# debouncersimple.net
KiCad netlist of a schematic drawn in EAGLE
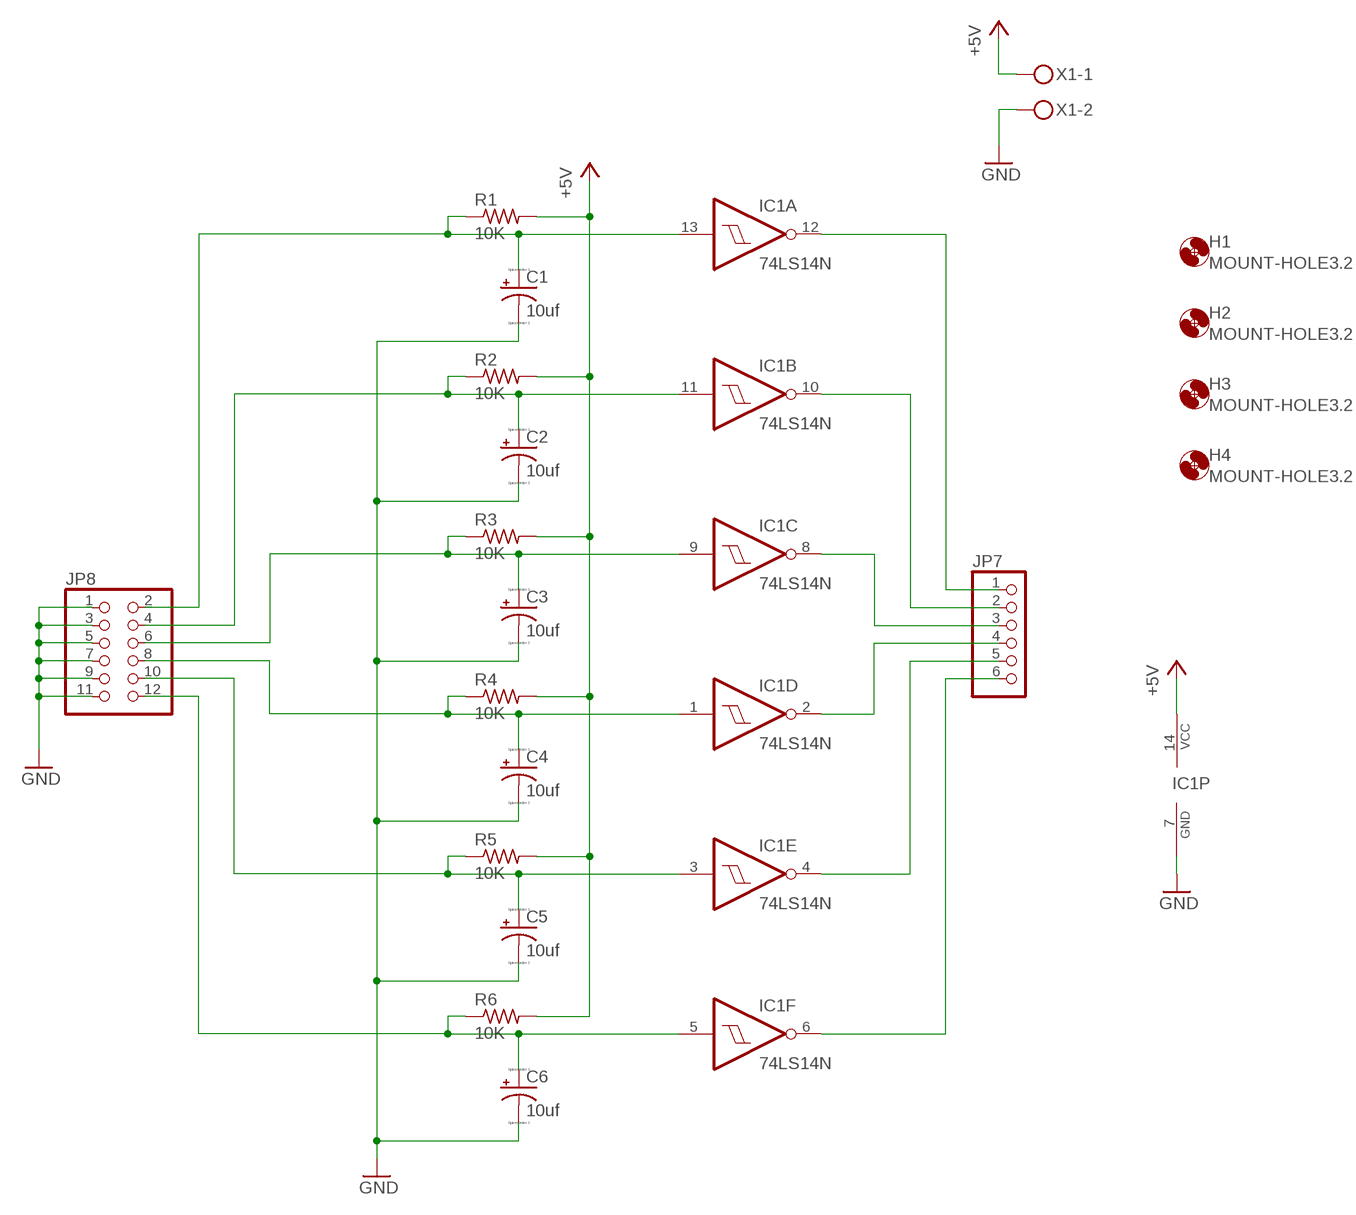
[diagram p0: schematic, sheet 1]

(export (version "E")
  (design (tool "Eeschema 10.0.6"))
  (components
    (comp (ref "C1")
      (value "10uf")
      (footprint "eagle-import:E2-5")
      (libsource (lib "eagle-import") (part "CPOL-USE2-5"))
    )
    (comp (ref "C2")
      (value "10uf")
      (footprint "eagle-import:E2-5")
      (libsource (lib "eagle-import") (part "CPOL-USE2-5"))
    )
    (comp (ref "C3")
      (value "10uf")
      (footprint "eagle-import:E2-5")
      (libsource (lib "eagle-import") (part "CPOL-USE2-5"))
    )
    (comp (ref "C4")
      (value "10uf")
      (footprint "eagle-import:E2-5")
      (libsource (lib "eagle-import") (part "CPOL-USE2-5"))
    )
    (comp (ref "C5")
      (value "10uf")
      (footprint "eagle-import:E2-5")
      (libsource (lib "eagle-import") (part "CPOL-USE2-5"))
    )
    (comp (ref "C6")
      (value "10uf")
      (footprint "eagle-import:E2-5")
      (libsource (lib "eagle-import") (part "CPOL-USE2-5"))
    )
    (comp (ref "H1")
      (value "MOUNT-HOLE3.2")
      (footprint "eagle-import:3,2")
      (libsource (lib "eagle-import") (part "MOUNT-HOLE3.2"))
    )
    (comp (ref "H2")
      (value "MOUNT-HOLE3.2")
      (footprint "eagle-import:3,2")
      (libsource (lib "eagle-import") (part "MOUNT-HOLE3.2"))
    )
    (comp (ref "H3")
      (value "MOUNT-HOLE3.2")
      (footprint "eagle-import:3,2")
      (libsource (lib "eagle-import") (part "MOUNT-HOLE3.2"))
    )
    (comp (ref "H4")
      (value "MOUNT-HOLE3.2")
      (footprint "eagle-import:3,2")
      (libsource (lib "eagle-import") (part "MOUNT-HOLE3.2"))
    )
    (comp (ref "IC1")
      (value "74LS14N")
      (footprint "eagle-import:DIL14")
      (libsource (lib "eagle-import") (part "7414NLS"))
    )
    (comp (ref "JP7")
      (value "PINHD-1X6")
      (footprint "eagle-import:1X06")
      (libsource (lib "eagle-import") (part "PINHD-1X6"))
    )
    (comp (ref "JP8")
      (value "PINHD-2X6")
      (footprint "eagle-import:2X06")
      (libsource (lib "eagle-import") (part "PINHD-2X6"))
    )
    (comp (ref "R1")
      (value "10K")
      (footprint "eagle-import:0207_2V")
      (libsource (lib "eagle-import") (part "R-US_0207/2V"))
    )
    (comp (ref "R2")
      (value "10K")
      (footprint "eagle-import:0207_2V")
      (libsource (lib "eagle-import") (part "R-US_0207/2V"))
    )
    (comp (ref "R3")
      (value "10K")
      (footprint "eagle-import:0207_2V")
      (libsource (lib "eagle-import") (part "R-US_0207/2V"))
    )
    (comp (ref "R4")
      (value "10K")
      (footprint "eagle-import:0207_2V")
      (libsource (lib "eagle-import") (part "R-US_0207/2V"))
    )
    (comp (ref "R5")
      (value "10K")
      (footprint "eagle-import:0207_2V")
      (libsource (lib "eagle-import") (part "R-US_0207/2V"))
    )
    (comp (ref "R6")
      (value "10K")
      (footprint "eagle-import:0207_2V")
      (libsource (lib "eagle-import") (part "R-US_0207/2V"))
    )
    (comp (ref "X1")
      (value "MKDSN1,5/2-5,08")
      (footprint "eagle-import:MKDSN1,5_2-5,08")
      (libsource (lib "eagle-import") (part "MKDSN1,5/2-5,08"))
    )
  )
  (nets
    (net (code "1") (name "+5V") (class "Default")
      (node (ref "IC1") (pin "14") (pinfunction "VCC_14") (pintype "power_in"))
      (node (ref "R1") (pin "2") (pinfunction "2_2") (pintype "passive"))
      (node (ref "R2") (pin "2") (pinfunction "2_2") (pintype "passive"))
      (node (ref "R3") (pin "2") (pinfunction "2_2") (pintype "passive"))
      (node (ref "R4") (pin "2") (pinfunction "2_2") (pintype "passive"))
      (node (ref "R5") (pin "2") (pinfunction "2_2") (pintype "passive"))
      (node (ref "R6") (pin "2") (pinfunction "2_2") (pintype "passive"))
      (node (ref "X1") (pin "1") (pinfunction "KL_1") (pintype "passive"))
    )
    (net (code "2") (name "GND") (class "Default")
      (node (ref "C1") (pin "-") (pinfunction "-_-") (pintype "passive"))
      (node (ref "C2") (pin "-") (pinfunction "-_-") (pintype "passive"))
      (node (ref "C3") (pin "-") (pinfunction "-_-") (pintype "passive"))
      (node (ref "C4") (pin "-") (pinfunction "-_-") (pintype "passive"))
      (node (ref "C5") (pin "-") (pinfunction "-_-") (pintype "passive"))
      (node (ref "C6") (pin "-") (pinfunction "-_-") (pintype "passive"))
      (node (ref "IC1") (pin "7") (pinfunction "GND_7") (pintype "power_in"))
      (node (ref "JP8") (pin "1") (pinfunction "1_1") (pintype "passive"))
      (node (ref "JP8") (pin "11") (pinfunction "11_11") (pintype "passive"))
      (node (ref "JP8") (pin "3") (pinfunction "3_3") (pintype "passive"))
      (node (ref "JP8") (pin "5") (pinfunction "5_5") (pintype "passive"))
      (node (ref "JP8") (pin "7") (pinfunction "7_7") (pintype "passive"))
      (node (ref "JP8") (pin "9") (pinfunction "9_9") (pintype "passive"))
      (node (ref "X1") (pin "2") (pinfunction "KL_2") (pintype "passive"))
    )
    (net (code "3") (name "Net-(IC1A-I)") (class "Default")
      (node (ref "C1") (pin "+") (pinfunction "+_+") (pintype "passive"))
      (node (ref "IC1") (pin "13") (pinfunction "I_13") (pintype "input"))
      (node (ref "JP8") (pin "2") (pinfunction "2_2") (pintype "passive"))
      (node (ref "R1") (pin "1") (pinfunction "1_1") (pintype "passive"))
    )
    (net (code "4") (name "Net-(IC1A-O)") (class "Default")
      (node (ref "IC1") (pin "12") (pinfunction "O_12") (pintype "output"))
      (node (ref "JP7") (pin "1") (pinfunction "1_1") (pintype "passive"))
    )
    (net (code "5") (name "Net-(IC1B-I)") (class "Default")
      (node (ref "C2") (pin "+") (pinfunction "+_+") (pintype "passive"))
      (node (ref "IC1") (pin "11") (pinfunction "I_11") (pintype "input"))
      (node (ref "JP8") (pin "4") (pinfunction "4_4") (pintype "passive"))
      (node (ref "R2") (pin "1") (pinfunction "1_1") (pintype "passive"))
    )
    (net (code "6") (name "Net-(IC1B-O)") (class "Default")
      (node (ref "IC1") (pin "10") (pinfunction "O_10") (pintype "output"))
      (node (ref "JP7") (pin "2") (pinfunction "2_2") (pintype "passive"))
    )
    (net (code "7") (name "Net-(IC1C-I)") (class "Default")
      (node (ref "C3") (pin "+") (pinfunction "+_+") (pintype "passive"))
      (node (ref "IC1") (pin "9") (pinfunction "I_9") (pintype "input"))
      (node (ref "JP8") (pin "6") (pinfunction "6_6") (pintype "passive"))
      (node (ref "R3") (pin "1") (pinfunction "1_1") (pintype "passive"))
    )
    (net (code "8") (name "Net-(IC1C-O)") (class "Default")
      (node (ref "IC1") (pin "8") (pinfunction "O_8") (pintype "output"))
      (node (ref "JP7") (pin "3") (pinfunction "3_3") (pintype "passive"))
    )
    (net (code "9") (name "Net-(IC1D-I)") (class "Default")
      (node (ref "C4") (pin "+") (pinfunction "+_+") (pintype "passive"))
      (node (ref "IC1") (pin "1") (pinfunction "I_1") (pintype "input"))
      (node (ref "JP8") (pin "8") (pinfunction "8_8") (pintype "passive"))
      (node (ref "R4") (pin "1") (pinfunction "1_1") (pintype "passive"))
    )
    (net (code "10") (name "Net-(IC1D-O)") (class "Default")
      (node (ref "IC1") (pin "2") (pinfunction "O_2") (pintype "output"))
      (node (ref "JP7") (pin "4") (pinfunction "4_4") (pintype "passive"))
    )
    (net (code "11") (name "Net-(IC1E-I)") (class "Default")
      (node (ref "C5") (pin "+") (pinfunction "+_+") (pintype "passive"))
      (node (ref "IC1") (pin "3") (pinfunction "I_3") (pintype "input"))
      (node (ref "JP8") (pin "10") (pinfunction "10_10") (pintype "passive"))
      (node (ref "R5") (pin "1") (pinfunction "1_1") (pintype "passive"))
    )
    (net (code "12") (name "Net-(IC1E-O)") (class "Default")
      (node (ref "IC1") (pin "4") (pinfunction "O_4") (pintype "output"))
      (node (ref "JP7") (pin "5") (pinfunction "5_5") (pintype "passive"))
    )
    (net (code "13") (name "Net-(IC1F-I)") (class "Default")
      (node (ref "C6") (pin "+") (pinfunction "+_+") (pintype "passive"))
      (node (ref "IC1") (pin "5") (pinfunction "I_5") (pintype "input"))
      (node (ref "JP8") (pin "12") (pinfunction "12_12") (pintype "passive"))
      (node (ref "R6") (pin "1") (pinfunction "1_1") (pintype "passive"))
    )
    (net (code "14") (name "Net-(IC1F-O)") (class "Default")
      (node (ref "IC1") (pin "6") (pinfunction "O_6") (pintype "output"))
      (node (ref "JP7") (pin "6") (pinfunction "6_6") (pintype "passive"))
    )
  )
)
